# Motor_Controller.net
KiCad netlist of a schematic drawn in Altium Designer
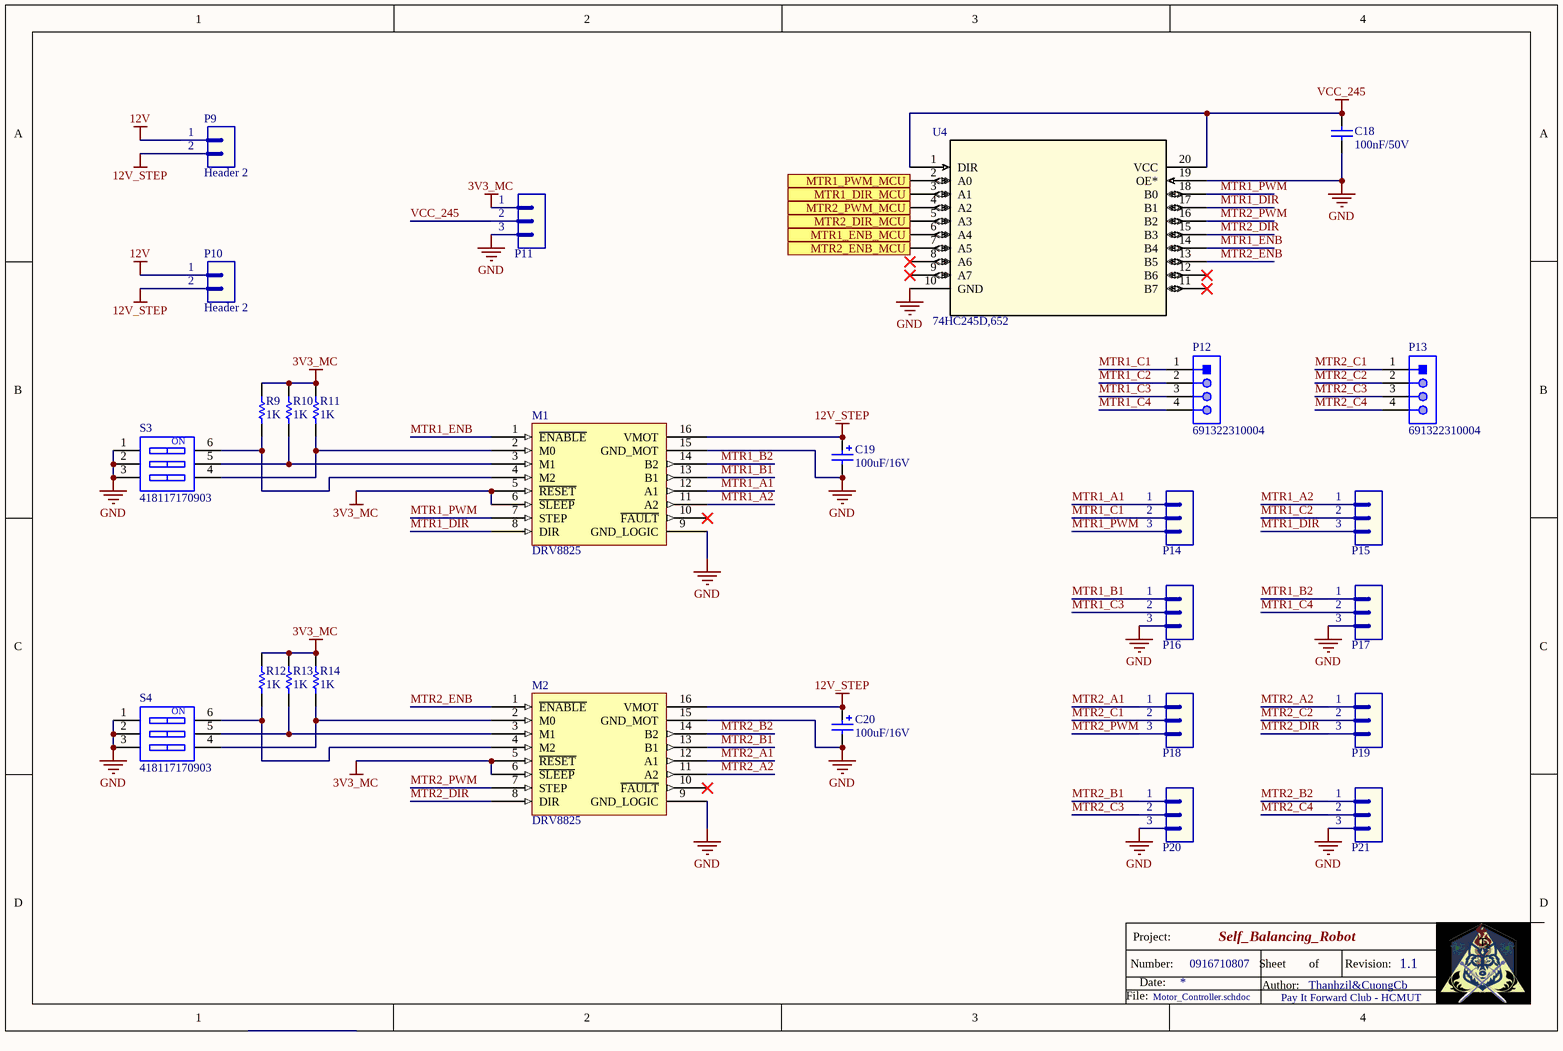
[diagram p0: Motor_Controller.SchDoc]

(export (version "E")
  (design (tool "Eeschema 10.0.6"))
  (components
    (comp (ref "C18")
      (value "100nF/50V")
      (footprint "CAP-SM-0805")
      (description "CAP CER 0.1UF 50V Y5V 0805")
      (fields
        (field (name "MANUFACTURER") "Samsung Electro-Mechanics")
        (field (name "MANUFACTURER PART NUMBER") "CL21F104ZBCNNNC")
      )
      (libsource (lib "Capacitor") (part "Cap-100nF-50V-0805"))
    )
    (comp (ref "C19")
      (value "100uF/16V")
      (footprint "CAP-SM-AL-SIZE-D-D6L6")
      (description "CAP ALUM 100UF 20% 16V SMD")
      (fields
        (field (name "MANUFACTURER") "Nichicon")
        (field (name "MANUFACTURER PART NUMBER") "UWX1C101MCL1GB")
      )
      (libsource (lib "Capacitor") (part "Cap-Al-100uF-16V-D6L5"))
    )
    (comp (ref "C20")
      (value "100uF/16V")
      (footprint "CAP-SM-AL-SIZE-D-D6L6")
      (description "CAP ALUM 100UF 20% 16V SMD")
      (fields
        (field (name "MANUFACTURER") "Nichicon")
        (field (name "MANUFACTURER PART NUMBER") "UWX1C101MCL1GB")
      )
      (libsource (lib "Capacitor") (part "Cap-Al-100uF-16V-D6L5"))
    )
    (comp (ref "M1")
      (value "DRV8825")
      (footprint "IC_DRV8825_STEPPER_MOTOR_DRIVER_CARRIER")
      (libsource (lib "Project_Xe_Can_Bang") (part "DRV8825"))
    )
    (comp (ref "M2")
      (value "DRV8825")
      (footprint "IC_DRV8825_STEPPER_MOTOR_DRIVER_CARRIER")
      (libsource (lib "Project_Xe_Can_Bang") (part "DRV8825"))
    )
    (comp (ref "P9")
      (value "Header 2")
      (footprint "Project_Xe_Can_Bang:JP2")
      (description "Header, 2-Pin")
      (fields (field (name "PUBLISHER") "Altium Limited"))
      (libsource (lib "Project_Xe_Can_Bang") (part "Header 2"))
    )
    (comp (ref "P10")
      (value "Header 2")
      (footprint "Project_Xe_Can_Bang:JP2")
      (description "Header, 2-Pin")
      (fields (field (name "PUBLISHER") "Altium Limited"))
      (libsource (lib "Project_Xe_Can_Bang") (part "Header 2"))
    )
    (comp (ref "P11")
      (value "Header 3")
      (footprint "Project_Xe_Can_Bang:JP3")
      (description "Header, 3-Pin")
      (fields (field (name "PUBLISHER") "Altium Limited"))
      (libsource (lib "Project_Xe_Can_Bang") (part "Header 3"))
    )
    (comp (ref "P12")
      (value "691322310004")
      (footprint "691322310004")
      (description "WR-TBL Serie 322 Horizontal PCB Header, Pluggable, pitch 3.81mm, 4p")
      (fields (field (name "PUBLISHER") "Wurth Elektronik"))
      (libsource (lib "Domino_691111710003_Altium_WR-TBL_rev19a") (part "691322310004"))
    )
    (comp (ref "P13")
      (value "691322310004")
      (footprint "691322310004")
      (description "WR-TBL Serie 322 Horizontal PCB Header, Pluggable, pitch 3.81mm, 4p")
      (fields (field (name "PUBLISHER") "Wurth Elektronik"))
      (libsource (lib "Domino_691111710003_Altium_WR-TBL_rev19a") (part "691322310004"))
    )
    (comp (ref "P14")
      (value "Header 3")
      (footprint "Project_Xe_Can_Bang:JP3")
      (description "Header, 3-Pin")
      (fields (field (name "PUBLISHER") "Altium Limited"))
      (libsource (lib "Project_Xe_Can_Bang") (part "Header 3"))
    )
    (comp (ref "P15")
      (value "Header 3")
      (footprint "Project_Xe_Can_Bang:JP3")
      (description "Header, 3-Pin")
      (fields (field (name "PUBLISHER") "Altium Limited"))
      (libsource (lib "Project_Xe_Can_Bang") (part "Header 3"))
    )
    (comp (ref "P16")
      (value "Header 3")
      (footprint "Project_Xe_Can_Bang:JP3")
      (description "Header, 3-Pin")
      (fields (field (name "PUBLISHER") "Altium Limited"))
      (libsource (lib "Project_Xe_Can_Bang") (part "Header 3"))
    )
    (comp (ref "P17")
      (value "Header 3")
      (footprint "Project_Xe_Can_Bang:JP3")
      (description "Header, 3-Pin")
      (fields (field (name "PUBLISHER") "Altium Limited"))
      (libsource (lib "Project_Xe_Can_Bang") (part "Header 3"))
    )
    (comp (ref "P18")
      (value "Header 3")
      (footprint "Project_Xe_Can_Bang:JP3")
      (description "Header, 3-Pin")
      (fields (field (name "PUBLISHER") "Altium Limited"))
      (libsource (lib "Project_Xe_Can_Bang") (part "Header 3"))
    )
    (comp (ref "P19")
      (value "Header 3")
      (footprint "Project_Xe_Can_Bang:JP3")
      (description "Header, 3-Pin")
      (fields (field (name "PUBLISHER") "Altium Limited"))
      (libsource (lib "Project_Xe_Can_Bang") (part "Header 3"))
    )
    (comp (ref "P20")
      (value "Header 3")
      (footprint "Project_Xe_Can_Bang:JP3")
      (description "Header, 3-Pin")
      (fields (field (name "PUBLISHER") "Altium Limited"))
      (libsource (lib "Project_Xe_Can_Bang") (part "Header 3"))
    )
    (comp (ref "P21")
      (value "Header 3")
      (footprint "Project_Xe_Can_Bang:JP3")
      (description "Header, 3-Pin")
      (fields (field (name "PUBLISHER") "Altium Limited"))
      (libsource (lib "Project_Xe_Can_Bang") (part "Header 3"))
    )
    (comp (ref "R9")
      (value "1K")
      (footprint "Resistor:RES-SM-0805")
      (description "RES 1K OHM 1% 1/4W 0805")
      (fields
        (field (name "MANUFACTURER") "Stackpole Electronics Inc")
        (field (name "MANUFACTURER PART NUMBER") "RNCP0805FTD1K00")
      )
      (libsource (lib "Resistor") (part "Res-1K-0805"))
    )
    (comp (ref "R10")
      (value "1K")
      (footprint "Resistor:RES-SM-0805")
      (description "RES 1K OHM 1% 1/4W 0805")
      (fields
        (field (name "MANUFACTURER") "Stackpole Electronics Inc")
        (field (name "MANUFACTURER PART NUMBER") "RNCP0805FTD1K00")
      )
      (libsource (lib "Resistor") (part "Res-1K-0805"))
    )
    (comp (ref "R11")
      (value "1K")
      (footprint "Resistor:RES-SM-0805")
      (description "RES 1K OHM 1% 1/4W 0805")
      (fields
        (field (name "MANUFACTURER") "Stackpole Electronics Inc")
        (field (name "MANUFACTURER PART NUMBER") "RNCP0805FTD1K00")
      )
      (libsource (lib "Resistor") (part "Res-1K-0805"))
    )
    (comp (ref "R12")
      (value "1K")
      (footprint "Resistor:RES-SM-0805")
      (description "RES 1K OHM 1% 1/4W 0805")
      (fields
        (field (name "MANUFACTURER") "Stackpole Electronics Inc")
        (field (name "MANUFACTURER PART NUMBER") "RNCP0805FTD1K00")
      )
      (libsource (lib "Resistor") (part "Res-1K-0805"))
    )
    (comp (ref "R13")
      (value "1K")
      (footprint "Resistor:RES-SM-0805")
      (description "RES 1K OHM 1% 1/4W 0805")
      (fields
        (field (name "MANUFACTURER") "Stackpole Electronics Inc")
        (field (name "MANUFACTURER PART NUMBER") "RNCP0805FTD1K00")
      )
      (libsource (lib "Resistor") (part "Res-1K-0805"))
    )
    (comp (ref "R14")
      (value "1K")
      (footprint "Resistor:RES-SM-0805")
      (description "RES 1K OHM 1% 1/4W 0805")
      (fields
        (field (name "MANUFACTURER") "Stackpole Electronics Inc")
        (field (name "MANUFACTURER PART NUMBER") "RNCP0805FTD1K00")
      )
      (libsource (lib "Resistor") (part "Res-1K-0805"))
    )
    (comp (ref "S3")
      (value "418117170903")
      (footprint "Project_Xe_Can_Bang:418117170903")
      (description "WS-DITV Compact THT Dip Switch, Flat Actuator, pitch 2.54mm, 3p")
      (fields (field (name "PUBLISHER") "Wurth Elektronik"))
      (libsource (lib "Project_Xe_Can_Bang") (part "418117170903"))
    )
    (comp (ref "S4")
      (value "418117170903")
      (footprint "Project_Xe_Can_Bang:418117170903")
      (description "WS-DITV Compact THT Dip Switch, Flat Actuator, pitch 2.54mm, 3p")
      (fields (field (name "PUBLISHER") "Wurth Elektronik"))
      (libsource (lib "Project_Xe_Can_Bang") (part "418117170903"))
    )
    (comp (ref "U4")
      (value "74HC245D,652")
      (footprint "SOT163-1_NEX")
      (description "No Description Available")
      (fields (field (name "COPYRIGHT") "Copyright (C) 2016 Accelerated Designs. All rights reserved"))
      (libsource (lib "74HC245D_652_2020-06-19_16-38-41") (part "74HC245D,652"))
    )
  )
  (nets
    (net (code "1") (name "/MTR1_A1") (class "Default")
      (node (ref "M1") (pin "12") (pinfunction "A1_12") (pintype "output"))
      (node (ref "P14") (pin "1") (pinfunction "1_1") (pintype "passive"))
    )
    (net (code "2") (name "/MTR1_A2") (class "Default")
      (node (ref "M1") (pin "11") (pinfunction "A2_11") (pintype "output"))
      (node (ref "P15") (pin "1") (pinfunction "1_1") (pintype "passive"))
    )
    (net (code "3") (name "/MTR1_B1") (class "Default")
      (node (ref "M1") (pin "13") (pinfunction "B1_13") (pintype "output"))
      (node (ref "P16") (pin "1") (pinfunction "1_1") (pintype "passive"))
    )
    (net (code "4") (name "/MTR1_B2") (class "Default")
      (node (ref "M1") (pin "14") (pinfunction "B2_14") (pintype "output"))
      (node (ref "P17") (pin "1") (pinfunction "1_1") (pintype "passive"))
    )
    (net (code "5") (name "/MTR1_C1") (class "Default")
      (node (ref "P12") (pin "1") (pinfunction "1_1") (pintype "passive"))
      (node (ref "P14") (pin "2") (pinfunction "2_2") (pintype "passive"))
    )
    (net (code "6") (name "/MTR1_C2") (class "Default")
      (node (ref "P12") (pin "2") (pinfunction "2_2") (pintype "passive"))
      (node (ref "P15") (pin "2") (pinfunction "2_2") (pintype "passive"))
    )
    (net (code "7") (name "/MTR1_C3") (class "Default")
      (node (ref "P12") (pin "3") (pinfunction "3_3") (pintype "passive"))
      (node (ref "P16") (pin "2") (pinfunction "2_2") (pintype "passive"))
    )
    (net (code "8") (name "/MTR1_C4") (class "Default")
      (node (ref "P12") (pin "4") (pinfunction "4_4") (pintype "passive"))
      (node (ref "P17") (pin "2") (pinfunction "2_2") (pintype "passive"))
    )
    (net (code "9") (name "/MTR1_DIR") (class "Default")
      (node (ref "M1") (pin "8") (pinfunction "DIR_8") (pintype "input"))
      (node (ref "P15") (pin "3") (pinfunction "3_3") (pintype "passive"))
      (node (ref "U4") (pin "17") (pinfunction "B1_17") (pintype "bidirectional"))
    )
    (net (code "10") (name "/MTR1_DIR_MCU") (class "Default")
      (node (ref "U4") (pin "3") (pinfunction "A1_3") (pintype "bidirectional"))
    )
    (net (code "11") (name "/MTR1_ENB") (class "Default")
      (node (ref "M1") (pin "1") (pinfunction "~{ENABLE}_1") (pintype "input"))
      (node (ref "U4") (pin "14") (pinfunction "B4_14") (pintype "bidirectional"))
    )
    (net (code "12") (name "/MTR1_ENB_MCU") (class "Default")
      (node (ref "U4") (pin "6") (pinfunction "A4_6") (pintype "bidirectional"))
    )
    (net (code "13") (name "/MTR1_PWM") (class "Default")
      (node (ref "M1") (pin "7") (pinfunction "STEP_7") (pintype "input"))
      (node (ref "P14") (pin "3") (pinfunction "3_3") (pintype "passive"))
      (node (ref "U4") (pin "18") (pinfunction "B0_18") (pintype "bidirectional"))
    )
    (net (code "14") (name "/MTR1_PWM_MCU") (class "Default")
      (node (ref "U4") (pin "2") (pinfunction "A0_2") (pintype "bidirectional"))
    )
    (net (code "15") (name "/MTR2_A1") (class "Default")
      (node (ref "M2") (pin "12") (pinfunction "A1_12") (pintype "output"))
      (node (ref "P18") (pin "1") (pinfunction "1_1") (pintype "passive"))
    )
    (net (code "16") (name "/MTR2_A2") (class "Default")
      (node (ref "M2") (pin "11") (pinfunction "A2_11") (pintype "output"))
      (node (ref "P19") (pin "1") (pinfunction "1_1") (pintype "passive"))
    )
    (net (code "17") (name "/MTR2_B1") (class "Default")
      (node (ref "M2") (pin "13") (pinfunction "B1_13") (pintype "output"))
      (node (ref "P20") (pin "1") (pinfunction "1_1") (pintype "passive"))
    )
    (net (code "18") (name "/MTR2_B2") (class "Default")
      (node (ref "M2") (pin "14") (pinfunction "B2_14") (pintype "output"))
      (node (ref "P21") (pin "1") (pinfunction "1_1") (pintype "passive"))
    )
    (net (code "19") (name "/MTR2_C1") (class "Default")
      (node (ref "P13") (pin "1") (pinfunction "1_1") (pintype "passive"))
      (node (ref "P18") (pin "2") (pinfunction "2_2") (pintype "passive"))
    )
    (net (code "20") (name "/MTR2_C2") (class "Default")
      (node (ref "P13") (pin "2") (pinfunction "2_2") (pintype "passive"))
      (node (ref "P19") (pin "2") (pinfunction "2_2") (pintype "passive"))
    )
    (net (code "21") (name "/MTR2_C3") (class "Default")
      (node (ref "P13") (pin "3") (pinfunction "3_3") (pintype "passive"))
      (node (ref "P20") (pin "2") (pinfunction "2_2") (pintype "passive"))
    )
    (net (code "22") (name "/MTR2_C4") (class "Default")
      (node (ref "P13") (pin "4") (pinfunction "4_4") (pintype "passive"))
      (node (ref "P21") (pin "2") (pinfunction "2_2") (pintype "passive"))
    )
    (net (code "23") (name "/MTR2_DIR") (class "Default")
      (node (ref "M2") (pin "8") (pinfunction "DIR_8") (pintype "input"))
      (node (ref "P19") (pin "3") (pinfunction "3_3") (pintype "passive"))
      (node (ref "U4") (pin "15") (pinfunction "B3_15") (pintype "bidirectional"))
    )
    (net (code "24") (name "/MTR2_DIR_MCU") (class "Default")
      (node (ref "U4") (pin "5") (pinfunction "A3_5") (pintype "bidirectional"))
    )
    (net (code "25") (name "/MTR2_ENB") (class "Default")
      (node (ref "M2") (pin "1") (pinfunction "~{ENABLE}_1") (pintype "input"))
      (node (ref "U4") (pin "13") (pinfunction "B5_13") (pintype "bidirectional"))
    )
    (net (code "26") (name "/MTR2_ENB_MCU") (class "Default")
      (node (ref "U4") (pin "7") (pinfunction "A5_7") (pintype "bidirectional"))
    )
    (net (code "27") (name "/MTR2_PWM") (class "Default")
      (node (ref "M2") (pin "7") (pinfunction "STEP_7") (pintype "input"))
      (node (ref "P18") (pin "3") (pinfunction "3_3") (pintype "passive"))
      (node (ref "U4") (pin "16") (pinfunction "B2_16") (pintype "bidirectional"))
    )
    (net (code "28") (name "/MTR2_PWM_MCU") (class "Default")
      (node (ref "U4") (pin "4") (pinfunction "A2_4") (pintype "bidirectional"))
    )
    (net (code "29") (name "3V3_MC") (class "Default")
      (node (ref "M1") (pin "5") (pinfunction "~{RESET}_5") (pintype "input"))
      (node (ref "M1") (pin "6") (pinfunction "~{SLEEP}_6") (pintype "input"))
      (node (ref "M2") (pin "5") (pinfunction "~{RESET}_5") (pintype "input"))
      (node (ref "M2") (pin "6") (pinfunction "~{SLEEP}_6") (pintype "input"))
      (node (ref "P11") (pin "1") (pinfunction "1_1") (pintype "passive"))
      (node (ref "R10") (pin "1") (pinfunction "1_1") (pintype "passive"))
      (node (ref "R11") (pin "1") (pinfunction "1_1") (pintype "passive"))
      (node (ref "R12") (pin "1") (pinfunction "1_1") (pintype "passive"))
      (node (ref "R13") (pin "1") (pinfunction "1_1") (pintype "passive"))
      (node (ref "R14") (pin "1") (pinfunction "1_1") (pintype "passive"))
      (node (ref "R9") (pin "1") (pinfunction "1_1") (pintype "passive"))
    )
    (net (code "30") (name "12V") (class "Default")
      (node (ref "P10") (pin "1") (pinfunction "1_1") (pintype "passive"))
      (node (ref "P9") (pin "1") (pinfunction "1_1") (pintype "passive"))
    )
    (net (code "31") (name "12V_STEP") (class "Default")
      (node (ref "C19") (pin "1") (pinfunction "1_1") (pintype "passive"))
      (node (ref "C20") (pin "1") (pinfunction "1_1") (pintype "passive"))
      (node (ref "M1") (pin "16") (pinfunction "VMOT_16") (pintype "power_in"))
      (node (ref "M2") (pin "16") (pinfunction "VMOT_16") (pintype "power_in"))
      (node (ref "P10") (pin "2") (pinfunction "2_2") (pintype "passive"))
      (node (ref "P9") (pin "2") (pinfunction "2_2") (pintype "passive"))
    )
    (net (code "32") (name "GND") (class "Default")
      (node (ref "C18") (pin "1") (pinfunction "1_1") (pintype "passive"))
      (node (ref "C19") (pin "2") (pinfunction "2_2") (pintype "passive"))
      (node (ref "C20") (pin "2") (pinfunction "2_2") (pintype "passive"))
      (node (ref "M1") (pin "15") (pinfunction "GND_MOT_15") (pintype "passive"))
      (node (ref "M1") (pin "9") (pinfunction "GND_LOGIC_9") (pintype "passive"))
      (node (ref "M2") (pin "15") (pinfunction "GND_MOT_15") (pintype "passive"))
      (node (ref "M2") (pin "9") (pinfunction "GND_LOGIC_9") (pintype "passive"))
      (node (ref "P11") (pin "3") (pinfunction "3_3") (pintype "passive"))
      (node (ref "P16") (pin "3") (pinfunction "3_3") (pintype "passive"))
      (node (ref "P17") (pin "3") (pinfunction "3_3") (pintype "passive"))
      (node (ref "P20") (pin "3") (pinfunction "3_3") (pintype "passive"))
      (node (ref "P21") (pin "3") (pinfunction "3_3") (pintype "passive"))
      (node (ref "S3") (pin "1") (pinfunction "1_1") (pintype "passive"))
      (node (ref "S3") (pin "2") (pinfunction "2_2") (pintype "passive"))
      (node (ref "S3") (pin "3") (pinfunction "3_3") (pintype "passive"))
      (node (ref "S4") (pin "1") (pinfunction "1_1") (pintype "passive"))
      (node (ref "S4") (pin "2") (pinfunction "2_2") (pintype "passive"))
      (node (ref "S4") (pin "3") (pinfunction "3_3") (pintype "passive"))
      (node (ref "U4") (pin "10") (pinfunction "GND_10") (pintype "power_in"))
      (node (ref "U4") (pin "19") (pinfunction "OE*_19") (pintype "input"))
    )
    (net (code "33") (name "Net-(M1-M0)") (class "Default")
      (node (ref "M1") (pin "2") (pinfunction "M0_2") (pintype "input"))
      (node (ref "R11") (pin "2") (pinfunction "2_2") (pintype "passive"))
      (node (ref "S3") (pin "4") (pinfunction "4_4") (pintype "passive"))
    )
    (net (code "34") (name "Net-(M1-M1)") (class "Default")
      (node (ref "M1") (pin "3") (pinfunction "M1_3") (pintype "input"))
      (node (ref "R10") (pin "2") (pinfunction "2_2") (pintype "passive"))
      (node (ref "S3") (pin "5") (pinfunction "5_5") (pintype "passive"))
    )
    (net (code "35") (name "Net-(M1-M2)") (class "Default")
      (node (ref "M1") (pin "4") (pinfunction "M2_4") (pintype "input"))
      (node (ref "R9") (pin "2") (pinfunction "2_2") (pintype "passive"))
      (node (ref "S3") (pin "6") (pinfunction "6_6") (pintype "passive"))
    )
    (net (code "36") (name "Net-(M2-M0)") (class "Default")
      (node (ref "M2") (pin "2") (pinfunction "M0_2") (pintype "input"))
      (node (ref "R14") (pin "2") (pinfunction "2_2") (pintype "passive"))
      (node (ref "S4") (pin "4") (pinfunction "4_4") (pintype "passive"))
    )
    (net (code "37") (name "Net-(M2-M1)") (class "Default")
      (node (ref "M2") (pin "3") (pinfunction "M1_3") (pintype "input"))
      (node (ref "R13") (pin "2") (pinfunction "2_2") (pintype "passive"))
      (node (ref "S4") (pin "5") (pinfunction "5_5") (pintype "passive"))
    )
    (net (code "38") (name "Net-(M2-M2)") (class "Default")
      (node (ref "M2") (pin "4") (pinfunction "M2_4") (pintype "input"))
      (node (ref "R12") (pin "2") (pinfunction "2_2") (pintype "passive"))
      (node (ref "S4") (pin "6") (pinfunction "6_6") (pintype "passive"))
    )
    (net (code "39") (name "VCC_245") (class "Default")
      (node (ref "C18") (pin "2") (pinfunction "2_2") (pintype "passive"))
      (node (ref "P11") (pin "2") (pinfunction "2_2") (pintype "passive"))
      (node (ref "U4") (pin "1") (pinfunction "DIR_1") (pintype "input"))
      (node (ref "U4") (pin "20") (pinfunction "VCC_20") (pintype "power_in"))
    )
    (net (code "40") (name "unconnected-(M1-~{FAULT}-Pad10)") (class "Default")
      (node (ref "M1") (pin "10") (pinfunction "~{FAULT}_10") (pintype "output+no_connect"))
    )
    (net (code "41") (name "unconnected-(M2-~{FAULT}-Pad10)") (class "Default")
      (node (ref "M2") (pin "10") (pinfunction "~{FAULT}_10") (pintype "output+no_connect"))
    )
    (net (code "42") (name "unconnected-(U4-A6-Pad8)") (class "Default")
      (node (ref "U4") (pin "8") (pinfunction "A6_8") (pintype "bidirectional+no_connect"))
    )
    (net (code "43") (name "unconnected-(U4-A7-Pad9)") (class "Default")
      (node (ref "U4") (pin "9") (pinfunction "A7_9") (pintype "bidirectional+no_connect"))
    )
    (net (code "44") (name "unconnected-(U4-B6-Pad12)") (class "Default")
      (node (ref "U4") (pin "12") (pinfunction "B6_12") (pintype "bidirectional+no_connect"))
    )
    (net (code "45") (name "unconnected-(U4-B7-Pad11)") (class "Default")
      (node (ref "U4") (pin "11") (pinfunction "B7_11") (pintype "bidirectional+no_connect"))
    )
  )
)
